# SCH1.net
KiCad netlist of a schematic drawn in Altium Designer
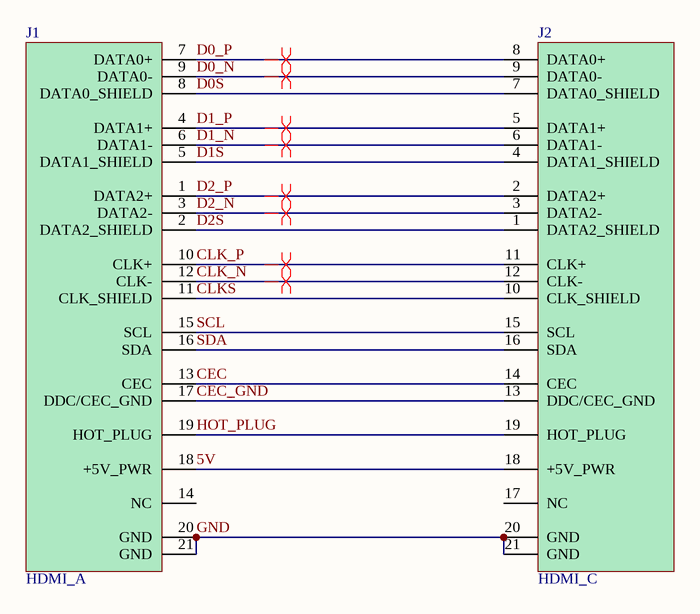
[diagram p0: SCH1.SchDoc]

(export (version "E")
  (design (tool "Eeschema 10.0.6"))
  (components
    (comp (ref "J1")
      (value "HDMI_A")
      (footprint "HDMI_A_Plug_19P")
      (description "HDMI A公头插板19pin")
      (libsource (lib "MT_Connector") (part "HDMI_A_Plug_19P"))
    )
    (comp (ref "J2")
      (value "HDMI_C")
      (footprint "HDMI_C_Plug_19P")
      (description "HDMI C公头插板19pin")
      (libsource (lib "MT_Connector") (part "HDMI_C_Plug_19P"))
    )
  )
  (nets
    (net (code "1") (name "/5V") (class "Default")
      (node (ref "J1") (pin "18") (pinfunction "+5V_PWR_18") (pintype "passive"))
      (node (ref "J2") (pin "18") (pinfunction "+5V_PWR_18") (pintype "passive"))
    )
    (net (code "2") (name "/CEC") (class "Default")
      (node (ref "J1") (pin "13") (pinfunction "CEC_13") (pintype "passive"))
      (node (ref "J2") (pin "14") (pinfunction "CEC_14") (pintype "passive"))
    )
    (net (code "3") (name "/CEC_GND") (class "Default")
      (node (ref "J1") (pin "17") (pinfunction "DDC/CEC_GND_17") (pintype "passive"))
      (node (ref "J2") (pin "13") (pinfunction "DDC/CEC_GND_13") (pintype "passive"))
    )
    (net (code "4") (name "/CLKS") (class "Default")
      (node (ref "J1") (pin "11") (pinfunction "CLK_SHIELD_11") (pintype "passive"))
      (node (ref "J2") (pin "10") (pinfunction "CLK_SHIELD_10") (pintype "passive"))
    )
    (net (code "5") (name "/CLK_N") (class "Default")
      (node (ref "J1") (pin "12") (pinfunction "CLK-_12") (pintype "passive"))
      (node (ref "J2") (pin "12") (pinfunction "CLK-_12") (pintype "passive"))
    )
    (net (code "6") (name "/CLK_P") (class "Default")
      (node (ref "J1") (pin "10") (pinfunction "CLK+_10") (pintype "passive"))
      (node (ref "J2") (pin "11") (pinfunction "CLK+_11") (pintype "passive"))
    )
    (net (code "7") (name "/D0S") (class "Default")
      (node (ref "J1") (pin "8") (pinfunction "DATA0_SHIELD_8") (pintype "passive"))
      (node (ref "J2") (pin "7") (pinfunction "DATA0_SHIELD_7") (pintype "passive"))
    )
    (net (code "8") (name "/D0_N") (class "Default")
      (node (ref "J1") (pin "9") (pinfunction "DATA0-_9") (pintype "passive"))
      (node (ref "J2") (pin "9") (pinfunction "DATA0-_9") (pintype "passive"))
    )
    (net (code "9") (name "/D0_P") (class "Default")
      (node (ref "J1") (pin "7") (pinfunction "DATA0+_7") (pintype "passive"))
      (node (ref "J2") (pin "8") (pinfunction "DATA0+_8") (pintype "passive"))
    )
    (net (code "10") (name "/D1S") (class "Default")
      (node (ref "J1") (pin "5") (pinfunction "DATA1_SHIELD_5") (pintype "passive"))
      (node (ref "J2") (pin "4") (pinfunction "DATA1_SHIELD_4") (pintype "passive"))
    )
    (net (code "11") (name "/D1_N") (class "Default")
      (node (ref "J1") (pin "6") (pinfunction "DATA1-_6") (pintype "passive"))
      (node (ref "J2") (pin "6") (pinfunction "DATA1-_6") (pintype "passive"))
    )
    (net (code "12") (name "/D1_P") (class "Default")
      (node (ref "J1") (pin "4") (pinfunction "DATA1+_4") (pintype "passive"))
      (node (ref "J2") (pin "5") (pinfunction "DATA1+_5") (pintype "passive"))
    )
    (net (code "13") (name "/D2S") (class "Default")
      (node (ref "J1") (pin "2") (pinfunction "DATA2_SHIELD_2") (pintype "passive"))
      (node (ref "J2") (pin "1") (pinfunction "DATA2_SHIELD_1") (pintype "passive"))
    )
    (net (code "14") (name "/D2_N") (class "Default")
      (node (ref "J1") (pin "3") (pinfunction "DATA2-_3") (pintype "passive"))
      (node (ref "J2") (pin "3") (pinfunction "DATA2-_3") (pintype "passive"))
    )
    (net (code "15") (name "/D2_P") (class "Default")
      (node (ref "J1") (pin "1") (pinfunction "DATA2+_1") (pintype "passive"))
      (node (ref "J2") (pin "2") (pinfunction "DATA2+_2") (pintype "passive"))
    )
    (net (code "16") (name "/GND") (class "Default")
      (node (ref "J1") (pin "20") (pinfunction "GND_20") (pintype "passive"))
      (node (ref "J1") (pin "21") (pinfunction "GND_21") (pintype "passive"))
      (node (ref "J2") (pin "20") (pinfunction "GND_20") (pintype "passive"))
      (node (ref "J2") (pin "21") (pinfunction "GND_21") (pintype "passive"))
    )
    (net (code "17") (name "/HOT_PLUG") (class "Default")
      (node (ref "J1") (pin "19") (pinfunction "HOT_PLUG_19") (pintype "passive"))
      (node (ref "J2") (pin "19") (pinfunction "HOT_PLUG_19") (pintype "passive"))
    )
    (net (code "18") (name "/SCL") (class "Default")
      (node (ref "J1") (pin "15") (pinfunction "SCL_15") (pintype "passive"))
      (node (ref "J2") (pin "15") (pinfunction "SCL_15") (pintype "passive"))
    )
    (net (code "19") (name "/SDA") (class "Default")
      (node (ref "J1") (pin "16") (pinfunction "SDA_16") (pintype "passive"))
      (node (ref "J2") (pin "16") (pinfunction "SDA_16") (pintype "passive"))
    )
    (net (code "20") (name "unconnected-(J1-NC-Pad14)") (class "Default")
      (node (ref "J1") (pin "14") (pinfunction "NC_14") (pintype "passive"))
    )
    (net (code "21") (name "unconnected-(J2-NC-Pad17)") (class "Default")
      (node (ref "J2") (pin "17") (pinfunction "NC_17") (pintype "passive"))
    )
  )
)
